# 04_-_RP2040.net
KiCad netlist of a schematic drawn in Altium Designer
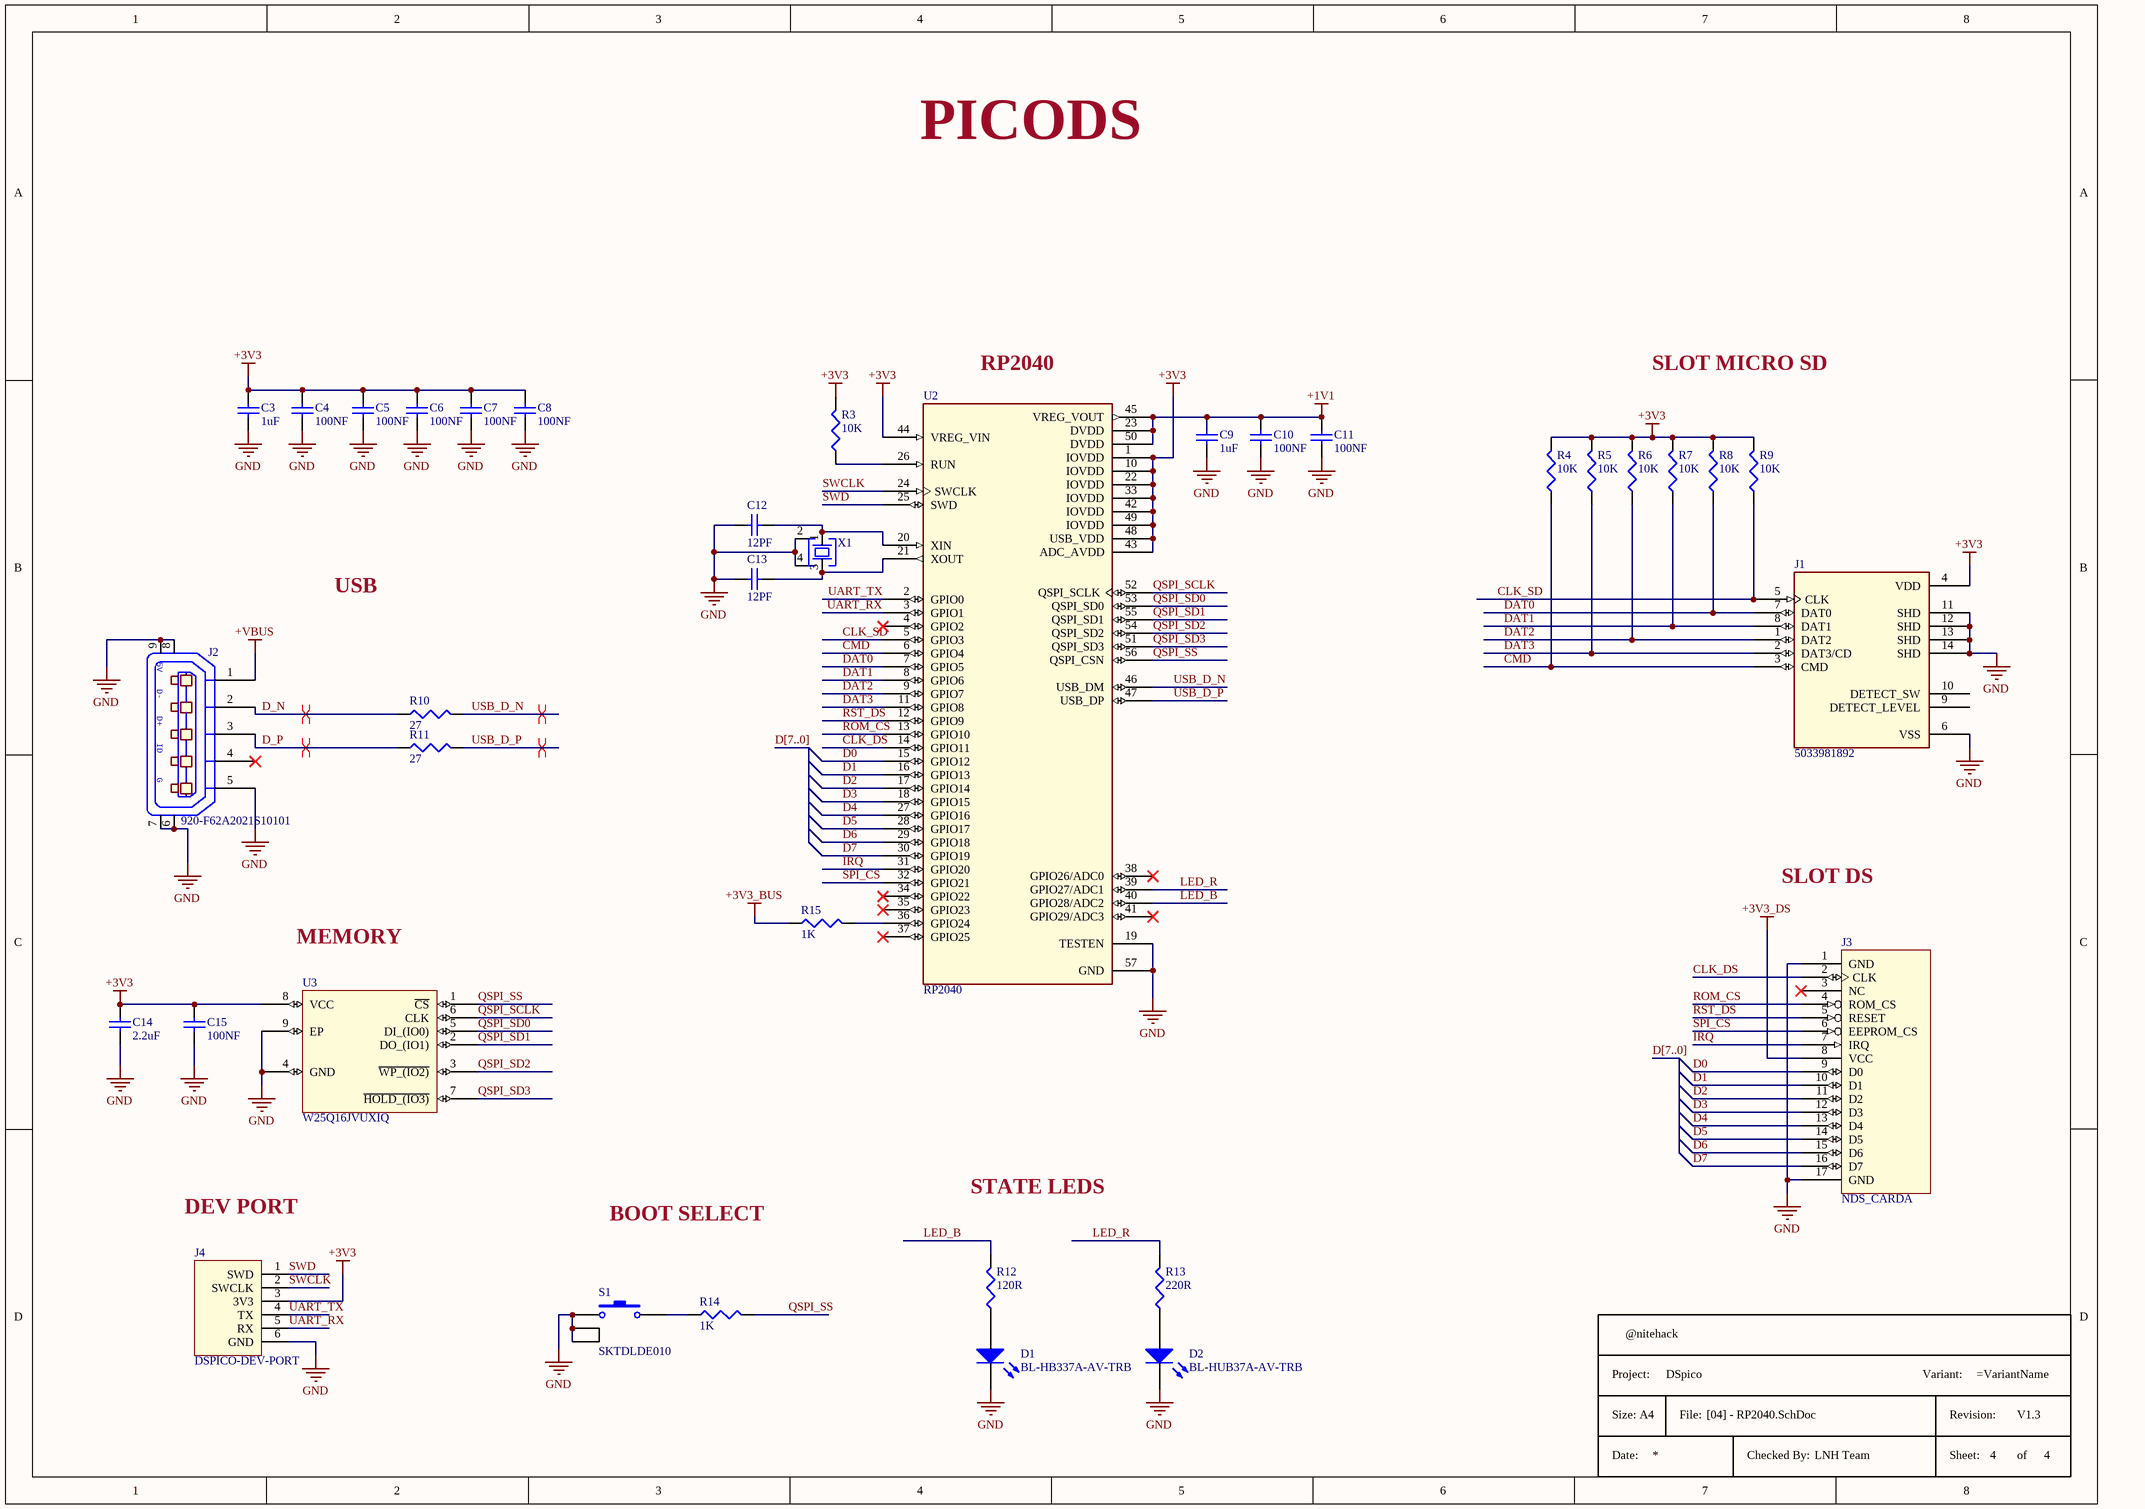
[diagram p0: [04] - RP2040.SchDoc]

(export (version "E")
  (design (tool "Eeschema 10.0.6"))
  (components
    (comp (ref "C3")
      (value "1uF")
      (footprint "C0402")
      (description "TDK - C1005X5R1E105K050BC - COND, CERÁ MULT, X5R, 1UF, 25V, 0402")
      (fields
        (field (name "MANUFACTURER") "TDK")
        (field (name "MANUFACTURER PART NUMBER") "C1005X5R1E105K050BC")
      )
      (libsource (lib "SCHLIB") (part "C1005X5R1E105K050BC"))
    )
    (comp (ref "C4")
      (value "100NF")
      (footprint "C0402")
      (description "0402 0.1 uF 16V ±10 % Tolerance X7R SMT Multilayer Ceramic Capacitor")
      (fields
        (field (name "MANUFACTURER") "Murata")
        (field (name "MANUFACTURER PART NUMBER") "GRM155R71C104KA88D")
      )
      (libsource (lib "SCHLIB") (part "GRM155R71C104KA88D"))
    )
    (comp (ref "C5")
      (value "100NF")
      (footprint "C0402")
      (description "0402 0.1 uF 16V ±10 % Tolerance X7R SMT Multilayer Ceramic Capacitor")
      (fields
        (field (name "MANUFACTURER") "Murata")
        (field (name "MANUFACTURER PART NUMBER") "GRM155R71C104KA88D")
      )
      (libsource (lib "SCHLIB") (part "GRM155R71C104KA88D"))
    )
    (comp (ref "C6")
      (value "100NF")
      (footprint "C0402")
      (description "0402 0.1 uF 16V ±10 % Tolerance X7R SMT Multilayer Ceramic Capacitor")
      (fields
        (field (name "MANUFACTURER") "Murata")
        (field (name "MANUFACTURER PART NUMBER") "GRM155R71C104KA88D")
      )
      (libsource (lib "SCHLIB") (part "GRM155R71C104KA88D"))
    )
    (comp (ref "C7")
      (value "100NF")
      (footprint "C0402")
      (description "0402 0.1 uF 16V ±10 % Tolerance X7R SMT Multilayer Ceramic Capacitor")
      (fields
        (field (name "MANUFACTURER") "Murata")
        (field (name "MANUFACTURER PART NUMBER") "GRM155R71C104KA88D")
      )
      (libsource (lib "SCHLIB") (part "GRM155R71C104KA88D"))
    )
    (comp (ref "C8")
      (value "100NF")
      (footprint "C0402")
      (description "0402 0.1 uF 16V ±10 % Tolerance X7R SMT Multilayer Ceramic Capacitor")
      (fields
        (field (name "MANUFACTURER") "Murata")
        (field (name "MANUFACTURER PART NUMBER") "GRM155R71C104KA88D")
      )
      (libsource (lib "SCHLIB") (part "GRM155R71C104KA88D"))
    )
    (comp (ref "C9")
      (value "1uF")
      (footprint "C0402")
      (description "TDK - C1005X5R1E105K050BC - COND, CERÁ MULT, X5R, 1UF, 25V, 0402")
      (fields
        (field (name "MANUFACTURER") "TDK")
        (field (name "MANUFACTURER PART NUMBER") "C1005X5R1E105K050BC")
      )
      (libsource (lib "SCHLIB") (part "C1005X5R1E105K050BC"))
    )
    (comp (ref "C10")
      (value "100NF")
      (footprint "C0402")
      (description "0402 0.1 uF 16V ±10 % Tolerance X7R SMT Multilayer Ceramic Capacitor")
      (fields
        (field (name "MANUFACTURER") "Murata")
        (field (name "MANUFACTURER PART NUMBER") "GRM155R71C104KA88D")
      )
      (libsource (lib "SCHLIB") (part "GRM155R71C104KA88D"))
    )
    (comp (ref "C11")
      (value "100NF")
      (footprint "C0402")
      (description "0402 0.1 uF 16V ±10 % Tolerance X7R SMT Multilayer Ceramic Capacitor")
      (fields
        (field (name "MANUFACTURER") "Murata")
        (field (name "MANUFACTURER PART NUMBER") "GRM155R71C104KA88D")
      )
      (libsource (lib "SCHLIB") (part "GRM155R71C104KA88D"))
    )
    (comp (ref "C12")
      (value "12PF")
      (footprint "C0402")
      (description "CAP CER 12PF 50V C0G/NP0 0402")
      (fields
        (field (name "MANUFACTURER") "Kyocera AVX")
        (field (name "MANUFACTURER PART NUMBER") "04025A120JAT2A")
      )
      (libsource (lib "SCHLIB") (part "04025A120JAT2A"))
    )
    (comp (ref "C13")
      (value "12PF")
      (footprint "C0402")
      (description "CAP CER 12PF 50V C0G/NP0 0402")
      (fields
        (field (name "MANUFACTURER") "Kyocera AVX")
        (field (name "MANUFACTURER PART NUMBER") "04025A120JAT2A")
      )
      (libsource (lib "SCHLIB") (part "04025A120JAT2A"))
    )
    (comp (ref "C14")
      (value "2.2uF")
      (footprint "C0402")
      (description "TDK - C1005X5R1A225K050BC - COND, CERÁ MULT, X5R, 2.2UF, 10V, 0402")
      (fields
        (field (name "MANUFACTURER") "TDK")
        (field (name "MANUFACTURER PART NUMBER") "C1005X5R1A225K050BC")
        (field (name ".PCBCHECK") "VMM")
        (field (name ".SCHCHECK") "VMM")
      )
      (libsource (lib "SCHLIB") (part "C1005X5R1A225K050BC"))
    )
    (comp (ref "C15")
      (value "100NF")
      (footprint "C0402")
      (description "0402 0.1 uF 16V ±10 % Tolerance X7R SMT Multilayer Ceramic Capacitor")
      (fields
        (field (name "MANUFACTURER") "Murata")
        (field (name "MANUFACTURER PART NUMBER") "GRM155R71C104KA88D")
      )
      (libsource (lib "SCHLIB") (part "GRM155R71C104KA88D"))
    )
    (comp (ref "D1")
      (value "BL-HB337A-AV-TRB")
      (footprint "LED0402-RD")
      (description "Blue 0402 1X.5X4MM")
      (fields (field (name "MANUFACTURER") "American Bright"))
      (libsource (lib "SCHLIB") (part "BL-HB337A-AV-TRB"))
    )
    (comp (ref "D2")
      (value "BL-HUB37A-AV-TRB")
      (footprint "LED0402-RD")
      (description "Red 0402 1X.5X4MM")
      (fields (field (name "MANUFACTURER") "American Bright"))
      (libsource (lib "SCHLIB") (part "BL-HUB37A-AV-TRB"))
    )
    (comp (ref "J1")
      (value "5033981892")
      (footprint "503398-1892_MOL")
      (libsource (lib "SCHLIB") (part "5033981892"))
    )
    (comp (ref "J2")
      (value "920-F62A2021S10101")
      (footprint "MICRO-USB_MICRO-USB-31")
      (libsource (lib "SCHLIB") (part "920-F62A2021S10101"))
    )
    (comp (ref "J3") (value "NDS_CARDA") (footprint "NDS_CARD") (libsource (lib "SCHLIB") (part "NDS_CARDA")))
    (comp (ref "J4")
      (value "DSPICO-DEV-PORT")
      (footprint "EP_DEV_PORT")
      (description "DSpico Development port")
      (fields
        (field (name "MANUFACTURER") "LNH")
        (field (name "MANUFACTURER PART NUMBER") "PICO-DEVELOP-PORT")
      )
      (libsource (lib "SCHLIB") (part "PICO-DEVELOP-PORT"))
    )
    (comp (ref "R3")
      (value "10K")
      (footprint "R0402")
      (description "VISHAY DRALORIC - CRCW040210K0FKED - RESISTENCIA, 10K, 0.063W, 1%, 0402, SMD")
      (fields
        (field (name "MANUFACTURER") "Vishay")
        (field (name "MANUFACTURER PART NUMBER") "CRCW040210K0FKED")
      )
      (libsource (lib "SCHLIB") (part "CRCW040210K0FKED"))
    )
    (comp (ref "R4")
      (value "10K")
      (footprint "R0402")
      (description "VISHAY DRALORIC - CRCW040210K0FKED - RESISTENCIA, 10K, 0.063W, 1%, 0402, SMD")
      (fields
        (field (name "MANUFACTURER") "Vishay")
        (field (name "MANUFACTURER PART NUMBER") "CRCW040210K0FKED")
      )
      (libsource (lib "SCHLIB") (part "CRCW040210K0FKED"))
    )
    (comp (ref "R5")
      (value "10K")
      (footprint "R0402")
      (description "VISHAY DRALORIC - CRCW040210K0FKED - RESISTENCIA, 10K, 0.063W, 1%, 0402, SMD")
      (fields
        (field (name "MANUFACTURER") "Vishay")
        (field (name "MANUFACTURER PART NUMBER") "CRCW040210K0FKED")
      )
      (libsource (lib "SCHLIB") (part "CRCW040210K0FKED"))
    )
    (comp (ref "R6")
      (value "10K")
      (footprint "R0402")
      (description "VISHAY DRALORIC - CRCW040210K0FKED - RESISTENCIA, 10K, 0.063W, 1%, 0402, SMD")
      (fields
        (field (name "MANUFACTURER") "Vishay")
        (field (name "MANUFACTURER PART NUMBER") "CRCW040210K0FKED")
      )
      (libsource (lib "SCHLIB") (part "CRCW040210K0FKED"))
    )
    (comp (ref "R7")
      (value "10K")
      (footprint "R0402")
      (description "VISHAY DRALORIC - CRCW040210K0FKED - RESISTENCIA, 10K, 0.063W, 1%, 0402, SMD")
      (fields
        (field (name "MANUFACTURER") "Vishay")
        (field (name "MANUFACTURER PART NUMBER") "CRCW040210K0FKED")
      )
      (libsource (lib "SCHLIB") (part "CRCW040210K0FKED"))
    )
    (comp (ref "R8")
      (value "10K")
      (footprint "R0402")
      (description "VISHAY DRALORIC - CRCW040210K0FKED - RESISTENCIA, 10K, 0.063W, 1%, 0402, SMD")
      (fields
        (field (name "MANUFACTURER") "Vishay")
        (field (name "MANUFACTURER PART NUMBER") "CRCW040210K0FKED")
      )
      (libsource (lib "SCHLIB") (part "CRCW040210K0FKED"))
    )
    (comp (ref "R9")
      (value "10K")
      (footprint "R0402")
      (description "VISHAY DRALORIC - CRCW040210K0FKED - RESISTENCIA, 10K, 0.063W, 1%, 0402, SMD")
      (fields
        (field (name "MANUFACTURER") "Vishay")
        (field (name "MANUFACTURER PART NUMBER") "CRCW040210K0FKED")
      )
      (libsource (lib "SCHLIB") (part "CRCW040210K0FKED"))
    )
    (comp (ref "R10")
      (value "27")
      (footprint "R0402")
      (description "RES 27 OHM 1% 1/16W 0402")
      (fields (field (name "TOLERANCE") "1%") (field (name "Comment") "RC0402FR-0727RL"))
      (libsource (lib "SCHLIB") (part "RC0402FR-0727RL"))
    )
    (comp (ref "R11")
      (value "27")
      (footprint "R0402")
      (description "RES 27 OHM 1% 1/16W 0402")
      (fields (field (name "TOLERANCE") "1%") (field (name "Comment") "RC0402FR-0727RL"))
      (libsource (lib "SCHLIB") (part "RC0402FR-0727RL"))
    )
    (comp (ref "R12")
      (value "120R")
      (footprint "R0402")
      (description "Res General Purpose Thick Film 0402 120 Ohm 1% 1/16W ±100ppm/°C Molded Paper T/R")
      (fields
        (field (name "MANUFACTURER") "Yageo")
        (field (name "MANUFACTURER PART NUMBER") "RC0402FR-07120RL")
      )
      (libsource (lib "SCHLIB") (part "RC0402FR-07120RL"))
    )
    (comp (ref "R13")
      (value "220R")
      (footprint "R0402")
      (description "SMD Chip Resistor, 220 Ohm, ± 1%, 62.5 mW, 0402 [1005 Metric], Thick Film, General Purpose")
      (fields
        (field (name "MANUFACTURER") "Yageo")
        (field (name "MANUFACTURER PART NUMBER") "RC0402FR-07220RL")
      )
      (libsource (lib "SCHLIB") (part "RC0402FR-07220RL"))
    )
    (comp (ref "R14")
      (value "1K")
      (footprint "R0402")
      (description "VISHAY - CRCW04021K00FKED - RES, PELÍC GRUESA, 1K, 1%, 0.063W, 0402")
      (fields
        (field (name "MANUFACTURER") "VISHAY")
        (field (name "MANUFACTURER PART NUMBER") "CRCW04021K00FKED")
      )
      (libsource (lib "SCHLIB") (part "CRCW04021K00FKEDC"))
    )
    (comp (ref "R15")
      (value "1K")
      (footprint "R0402")
      (description "VISHAY - CRCW04021K00FKED - RES, PELÍC GRUESA, 1K, 1%, 0.063W, 0402")
      (fields
        (field (name "MANUFACTURER") "VISHAY")
        (field (name "MANUFACTURER PART NUMBER") "CRCW04021K00FKED")
      )
      (libsource (lib "SCHLIB") (part "CRCW04021K00FKEDC"))
    )
    (comp (ref "S1")
      (value "SKTDLDE010")
      (footprint "KEY-SMD_SKTDLDE010")
      (description "Switch Tactile N.O. SPST Rectangular Button Gull Wing 0.05A 12VDC 1.6N SMD T/R")
      (fields (field (name "MANUFACTURER") "Alps Electric"))
      (libsource (lib "SCHLIB") (part "SKTDLDE010"))
    )
    (comp (ref "U2")
      (value "RP2040")
      (footprint "QFN40P700X700X90-57N")
      (description "RP2040 chip for Raspberry Pi Pico - ARM Cortex-M0+ MCU 32-Bit")
      (fields (field (name "MF") "Raspberry Pi"))
      (libsource (lib "SCHLIB") (part "RP2040"))
    )
    (comp (ref "U3")
      (value "W25Q16JVUXIQ")
      (footprint "SON50P300X200X60-9N")
      (description "NOR Flash Serial (SPI, Dual SPI, Quad SPI) 3V/3.3V 16M-bit 2M x 8 6ns 8-Pin USON EP T/R")
      (fields (field (name "MF") "Winbond"))
      (libsource (lib "SCHLIB") (part "W25Q16JVUXIQ"))
    )
    (comp (ref "X1")
      (value "XYDBPCNANF-12MHZ")
      (footprint "OSC-SMD_4P-L2.5-W2.0-BL")
      (libsource (lib "SCHLIB") (part "XYDBPCNANF-12MHZ"))
    )
  )
  (nets
    (net (code "1") (name "+1V1") (class "Default")
      (node (ref "C10") (pin "2") (pinfunction "2_2") (pintype "passive"))
      (node (ref "C11") (pin "2") (pinfunction "2_2") (pintype "passive"))
      (node (ref "C9") (pin "2") (pinfunction "2_2") (pintype "passive"))
      (node (ref "U2") (pin "23") (pinfunction "DVDD_23") (pintype "power_in"))
      (node (ref "U2") (pin "45") (pinfunction "VREG_VOUT_45") (pintype "output"))
      (node (ref "U2") (pin "50") (pinfunction "DVDD_50") (pintype "power_in"))
    )
    (net (code "2") (name "+3V3") (class "Default")
      (node (ref "C14") (pin "2") (pinfunction "2_2") (pintype "passive"))
      (node (ref "C15") (pin "2") (pinfunction "2_2") (pintype "passive"))
      (node (ref "C3") (pin "2") (pinfunction "2_2") (pintype "passive"))
      (node (ref "C4") (pin "2") (pinfunction "2_2") (pintype "passive"))
      (node (ref "C5") (pin "2") (pinfunction "2_2") (pintype "passive"))
      (node (ref "C6") (pin "2") (pinfunction "2_2") (pintype "passive"))
      (node (ref "C7") (pin "2") (pinfunction "2_2") (pintype "passive"))
      (node (ref "C8") (pin "2") (pinfunction "2_2") (pintype "passive"))
      (node (ref "J1") (pin "4") (pinfunction "VDD_4") (pintype "power_in"))
      (node (ref "J4") (pin "3") (pinfunction "3V3_3") (pintype "passive"))
      (node (ref "R3") (pin "2") (pinfunction "2_2") (pintype "passive"))
      (node (ref "R4") (pin "2") (pinfunction "2_2") (pintype "passive"))
      (node (ref "R5") (pin "2") (pinfunction "2_2") (pintype "passive"))
      (node (ref "R6") (pin "2") (pinfunction "2_2") (pintype "passive"))
      (node (ref "R7") (pin "2") (pinfunction "2_2") (pintype "passive"))
      (node (ref "R8") (pin "2") (pinfunction "2_2") (pintype "passive"))
      (node (ref "R9") (pin "2") (pinfunction "2_2") (pintype "passive"))
      (node (ref "U2") (pin "1") (pinfunction "IOVDD_1") (pintype "power_in"))
      (node (ref "U2") (pin "10") (pinfunction "IOVDD_10") (pintype "power_in"))
      (node (ref "U2") (pin "22") (pinfunction "IOVDD_22") (pintype "power_in"))
      (node (ref "U2") (pin "33") (pinfunction "IOVDD_33") (pintype "power_in"))
      (node (ref "U2") (pin "42") (pinfunction "IOVDD_42") (pintype "power_in"))
      (node (ref "U2") (pin "43") (pinfunction "ADC_AVDD_43") (pintype "power_in"))
      (node (ref "U2") (pin "44") (pinfunction "VREG_VIN_44") (pintype "input"))
      (node (ref "U2") (pin "48") (pinfunction "USB_VDD_48") (pintype "power_in"))
      (node (ref "U2") (pin "49") (pinfunction "IOVDD_49") (pintype "power_in"))
      (node (ref "U3") (pin "8") (pinfunction "VCC_8") (pintype "bidirectional"))
    )
    (net (code "3") (name "+3V3_BUS") (class "Default")
      (node (ref "R15") (pin "1") (pinfunction "1_1") (pintype "passive"))
    )
    (net (code "4") (name "+3V3_DS") (class "Default")
      (node (ref "J3") (pin "8") (pinfunction "VCC_8") (pintype "power_in"))
    )
    (net (code "5") (name "+VBUS") (class "Default")
      (node (ref "J2") (pin "1") (pinfunction "P1_1") (pintype "passive"))
    )
    (net (code "6") (name "/CLK_DS") (class "Default")
      (node (ref "J3") (pin "2") (pinfunction "CLK_2") (pintype "bidirectional"))
      (node (ref "U2") (pin "14") (pinfunction "GPIO11_14") (pintype "bidirectional"))
    )
    (net (code "7") (name "/CLK_SD") (class "Default")
      (node (ref "J1") (pin "5") (pinfunction "CLK_5") (pintype "input"))
      (node (ref "R9") (pin "1") (pinfunction "1_1") (pintype "passive"))
      (node (ref "U2") (pin "5") (pinfunction "GPIO3_5") (pintype "bidirectional"))
    )
    (net (code "8") (name "/CMD") (class "Default")
      (node (ref "J1") (pin "3") (pinfunction "CMD_3") (pintype "bidirectional"))
      (node (ref "R4") (pin "1") (pinfunction "1_1") (pintype "passive"))
      (node (ref "U2") (pin "6") (pinfunction "GPIO4_6") (pintype "bidirectional"))
    )
    (net (code "9") (name "/D0") (class "Default")
      (node (ref "J3") (pin "9") (pinfunction "D0_9") (pintype "bidirectional"))
      (node (ref "U2") (pin "15") (pinfunction "GPIO12_15") (pintype "bidirectional"))
    )
    (net (code "10") (name "/D1") (class "Default")
      (node (ref "J3") (pin "10") (pinfunction "D1_10") (pintype "bidirectional"))
      (node (ref "U2") (pin "16") (pinfunction "GPIO13_16") (pintype "bidirectional"))
    )
    (net (code "11") (name "/D2") (class "Default")
      (node (ref "J3") (pin "11") (pinfunction "D2_11") (pintype "bidirectional"))
      (node (ref "U2") (pin "17") (pinfunction "GPIO14_17") (pintype "bidirectional"))
    )
    (net (code "12") (name "/D3") (class "Default")
      (node (ref "J3") (pin "12") (pinfunction "D3_12") (pintype "bidirectional"))
      (node (ref "U2") (pin "18") (pinfunction "GPIO15_18") (pintype "bidirectional"))
    )
    (net (code "13") (name "/D4") (class "Default")
      (node (ref "J3") (pin "13") (pinfunction "D4_13") (pintype "bidirectional"))
      (node (ref "U2") (pin "27") (pinfunction "GPIO16_27") (pintype "bidirectional"))
    )
    (net (code "14") (name "/D5") (class "Default")
      (node (ref "J3") (pin "14") (pinfunction "D5_14") (pintype "bidirectional"))
      (node (ref "U2") (pin "28") (pinfunction "GPIO17_28") (pintype "bidirectional"))
    )
    (net (code "15") (name "/D6") (class "Default")
      (node (ref "J3") (pin "15") (pinfunction "D6_15") (pintype "bidirectional"))
      (node (ref "U2") (pin "29") (pinfunction "GPIO18_29") (pintype "bidirectional"))
    )
    (net (code "16") (name "/D7") (class "Default")
      (node (ref "J3") (pin "16") (pinfunction "D7_16") (pintype "bidirectional"))
      (node (ref "U2") (pin "30") (pinfunction "GPIO19_30") (pintype "bidirectional"))
    )
    (net (code "17") (name "/DAT0") (class "Default")
      (node (ref "J1") (pin "7") (pinfunction "DAT0_7") (pintype "bidirectional"))
      (node (ref "R8") (pin "1") (pinfunction "1_1") (pintype "passive"))
      (node (ref "U2") (pin "7") (pinfunction "GPIO5_7") (pintype "bidirectional"))
    )
    (net (code "18") (name "/DAT1") (class "Default")
      (node (ref "J1") (pin "8") (pinfunction "DAT1_8") (pintype "bidirectional"))
      (node (ref "R7") (pin "1") (pinfunction "1_1") (pintype "passive"))
      (node (ref "U2") (pin "8") (pinfunction "GPIO6_8") (pintype "bidirectional"))
    )
    (net (code "19") (name "/DAT2") (class "Default")
      (node (ref "J1") (pin "1") (pinfunction "DAT2_1") (pintype "bidirectional"))
      (node (ref "R6") (pin "1") (pinfunction "1_1") (pintype "passive"))
      (node (ref "U2") (pin "9") (pinfunction "GPIO7_9") (pintype "bidirectional"))
    )
    (net (code "20") (name "/DAT3") (class "Default")
      (node (ref "J1") (pin "2") (pinfunction "DAT3/CD_2") (pintype "bidirectional"))
      (node (ref "R5") (pin "1") (pinfunction "1_1") (pintype "passive"))
      (node (ref "U2") (pin "11") (pinfunction "GPIO8_11") (pintype "bidirectional"))
    )
    (net (code "22") (name "/D_N") (class "Default")
      (node (ref "J2") (pin "2") (pinfunction "P2_2") (pintype "passive"))
      (node (ref "R10") (pin "1") (pinfunction "1_1") (pintype "passive"))
    )
    (net (code "23") (name "/D_P") (class "Default")
      (node (ref "J2") (pin "3") (pinfunction "P3_3") (pintype "passive"))
      (node (ref "R11") (pin "1") (pinfunction "1_1") (pintype "passive"))
    )
    (net (code "24") (name "/IRQ") (class "Default")
      (node (ref "J3") (pin "7") (pinfunction "IRQ_7") (pintype "input"))
      (node (ref "U2") (pin "31") (pinfunction "GPIO20_31") (pintype "bidirectional"))
    )
    (net (code "25") (name "/LED_B") (class "Default")
      (node (ref "R12") (pin "2") (pinfunction "2_2") (pintype "passive"))
      (node (ref "U2") (pin "40") (pinfunction "GPIO28/ADC2_40") (pintype "bidirectional"))
    )
    (net (code "26") (name "/LED_R") (class "Default")
      (node (ref "R13") (pin "2") (pinfunction "2_2") (pintype "passive"))
      (node (ref "U2") (pin "39") (pinfunction "GPIO27/ADC1_39") (pintype "bidirectional"))
    )
    (net (code "27") (name "/QSPI_SCLK") (class "Default")
      (node (ref "U2") (pin "52") (pinfunction "QSPI_SCLK_52") (pintype "bidirectional"))
      (node (ref "U3") (pin "6") (pinfunction "CLK_6") (pintype "bidirectional"))
    )
    (net (code "28") (name "/QSPI_SD0") (class "Default")
      (node (ref "U2") (pin "53") (pinfunction "QSPI_SD0_53") (pintype "bidirectional"))
      (node (ref "U3") (pin "5") (pinfunction "DI_(IO0)_5") (pintype "bidirectional"))
    )
    (net (code "29") (name "/QSPI_SD1") (class "Default")
      (node (ref "U2") (pin "55") (pinfunction "QSPI_SD1_55") (pintype "bidirectional"))
      (node (ref "U3") (pin "2") (pinfunction "DO_(IO1)_2") (pintype "bidirectional"))
    )
    (net (code "30") (name "/QSPI_SD2") (class "Default")
      (node (ref "U2") (pin "54") (pinfunction "QSPI_SD2_54") (pintype "bidirectional"))
      (node (ref "U3") (pin "3") (pinfunction "~{WP_(IO2)}_3") (pintype "bidirectional"))
    )
    (net (code "31") (name "/QSPI_SD3") (class "Default")
      (node (ref "U2") (pin "51") (pinfunction "QSPI_SD3_51") (pintype "bidirectional"))
      (node (ref "U3") (pin "7") (pinfunction "~{HOLD_(IO3)}_7") (pintype "bidirectional"))
    )
    (net (code "32") (name "/QSPI_SS") (class "Default")
      (node (ref "R14") (pin "2") (pinfunction "2_2") (pintype "passive"))
      (node (ref "U2") (pin "56") (pinfunction "QSPI_CSN_56") (pintype "bidirectional"))
      (node (ref "U3") (pin "1") (pinfunction "~{CS}_1") (pintype "bidirectional"))
    )
    (net (code "33") (name "/ROM_CS") (class "Default")
      (node (ref "J3") (pin "4") (pinfunction "ROM_CS_4") (pintype "input"))
      (node (ref "U2") (pin "13") (pinfunction "GPIO10_13") (pintype "bidirectional"))
    )
    (net (code "34") (name "/RST_DS") (class "Default")
      (node (ref "J3") (pin "5") (pinfunction "RESET_5") (pintype "input"))
      (node (ref "U2") (pin "12") (pinfunction "GPIO9_12") (pintype "bidirectional"))
    )
    (net (code "35") (name "/SPI_CS") (class "Default")
      (node (ref "J3") (pin "6") (pinfunction "EEPROM_CS_6") (pintype "input"))
      (node (ref "U2") (pin "32") (pinfunction "GPIO21_32") (pintype "bidirectional"))
    )
    (net (code "36") (name "/SWCLK") (class "Default")
      (node (ref "J4") (pin "2") (pinfunction "SWCLK_2") (pintype "passive"))
      (node (ref "U2") (pin "24") (pinfunction "SWCLK_24") (pintype "input"))
    )
    (net (code "37") (name "/SWD") (class "Default")
      (node (ref "J4") (pin "1") (pinfunction "SWD_1") (pintype "passive"))
      (node (ref "U2") (pin "25") (pinfunction "SWD_25") (pintype "bidirectional"))
    )
    (net (code "38") (name "/UART_RX") (class "Default")
      (node (ref "J4") (pin "5") (pinfunction "RX_5") (pintype "passive"))
      (node (ref "U2") (pin "3") (pinfunction "GPIO1_3") (pintype "bidirectional"))
    )
    (net (code "39") (name "/UART_TX") (class "Default")
      (node (ref "J4") (pin "4") (pinfunction "TX_4") (pintype "passive"))
      (node (ref "U2") (pin "2") (pinfunction "GPIO0_2") (pintype "bidirectional"))
    )
    (net (code "40") (name "/USB_D_N") (class "Default")
      (node (ref "R10") (pin "2") (pinfunction "2_2") (pintype "passive"))
      (node (ref "U2") (pin "46") (pinfunction "USB_DM_46") (pintype "bidirectional"))
    )
    (net (code "41") (name "/USB_D_P") (class "Default")
      (node (ref "R11") (pin "2") (pinfunction "2_2") (pintype "passive"))
      (node (ref "U2") (pin "47") (pinfunction "USB_DP_47") (pintype "bidirectional"))
    )
    (net (code "42") (name "GND") (class "Default")
      (node (ref "C10") (pin "1") (pinfunction "1_1") (pintype "passive"))
      (node (ref "C11") (pin "1") (pinfunction "1_1") (pintype "passive"))
      (node (ref "C12") (pin "1") (pinfunction "1_1") (pintype "passive"))
      (node (ref "C13") (pin "1") (pinfunction "1_1") (pintype "passive"))
      (node (ref "C14") (pin "1") (pinfunction "1_1") (pintype "passive"))
      (node (ref "C15") (pin "1") (pinfunction "1_1") (pintype "passive"))
      (node (ref "C3") (pin "1") (pinfunction "1_1") (pintype "passive"))
      (node (ref "C4") (pin "1") (pinfunction "1_1") (pintype "passive"))
      (node (ref "C5") (pin "1") (pinfunction "1_1") (pintype "passive"))
      (node (ref "C6") (pin "1") (pinfunction "1_1") (pintype "passive"))
      (node (ref "C7") (pin "1") (pinfunction "1_1") (pintype "passive"))
      (node (ref "C8") (pin "1") (pinfunction "1_1") (pintype "passive"))
      (node (ref "C9") (pin "1") (pinfunction "1_1") (pintype "passive"))
      (node (ref "D1") (pin "1") (pinfunction "1_1") (pintype "passive"))
      (node (ref "D2") (pin "1") (pinfunction "1_1") (pintype "passive"))
      (node (ref "J1") (pin "11") (pinfunction "SHD_11") (pintype "passive"))
      (node (ref "J1") (pin "12") (pinfunction "SHD_12") (pintype "passive"))
      (node (ref "J1") (pin "13") (pinfunction "SHD_13") (pintype "passive"))
      (node (ref "J1") (pin "14") (pinfunction "SHD_14") (pintype "passive"))
      (node (ref "J1") (pin "6") (pinfunction "VSS_6") (pintype "power_in"))
      (node (ref "J2") (pin "5") (pinfunction "P5_5") (pintype "passive"))
      (node (ref "J2") (pin "6") (pinfunction "6_6") (pintype "passive"))
      (node (ref "J2") (pin "7") (pinfunction "7_7") (pintype "passive"))
      (node (ref "J2") (pin "8") (pinfunction "8_8") (pintype "passive"))
      (node (ref "J2") (pin "9") (pinfunction "9_9") (pintype "passive"))
      (node (ref "J3") (pin "1") (pinfunction "GND_1") (pintype "power_in"))
      (node (ref "J3") (pin "17") (pinfunction "GND_17") (pintype "power_in"))
      (node (ref "J4") (pin "6") (pinfunction "GND_6") (pintype "passive"))
      (node (ref "S1") (pin "1") (pinfunction "1_1") (pintype "passive"))
      (node (ref "S1") (pin "3") (pinfunction "3_3") (pintype "passive"))
      (node (ref "S1") (pin "4") (pinfunction "4_4") (pintype "passive"))
      (node (ref "U2") (pin "19") (pinfunction "TESTEN_19") (pintype "passive"))
      (node (ref "U2") (pin "57") (pinfunction "GND_57") (pintype "power_in"))
      (node (ref "U3") (pin "4") (pinfunction "GND_4") (pintype "bidirectional"))
      (node (ref "U3") (pin "9") (pinfunction "EP_9") (pintype "bidirectional"))
      (node (ref "X1") (pin "2") (pinfunction "2_2") (pintype "passive"))
      (node (ref "X1") (pin "4") (pinfunction "4_4") (pintype "passive"))
    )
    (net (code "43") (name "Net-(D1-Pad2)") (class "Default")
      (node (ref "D1") (pin "2") (pinfunction "2_2") (pintype "passive"))
      (node (ref "R12") (pin "1") (pinfunction "1_1") (pintype "passive"))
    )
    (net (code "44") (name "Net-(D2-Pad2)") (class "Default")
      (node (ref "D2") (pin "2") (pinfunction "2_2") (pintype "passive"))
      (node (ref "R13") (pin "1") (pinfunction "1_1") (pintype "passive"))
    )
    (net (code "45") (name "Net-(R14-Pad1)") (class "Default")
      (node (ref "R14") (pin "1") (pinfunction "1_1") (pintype "passive"))
      (node (ref "S1") (pin "2") (pinfunction "2_2") (pintype "passive"))
    )
    (net (code "46") (name "Net-(U2-GPIO24)") (class "Default")
      (node (ref "R15") (pin "2") (pinfunction "2_2") (pintype "passive"))
      (node (ref "U2") (pin "36") (pinfunction "GPIO24_36") (pintype "bidirectional"))
    )
    (net (code "47") (name "Net-(U2-RUN)") (class "Default")
      (node (ref "R3") (pin "1") (pinfunction "1_1") (pintype "passive"))
      (node (ref "U2") (pin "26") (pinfunction "RUN_26") (pintype "input"))
    )
    (net (code "48") (name "Net-(U2-XIN)") (class "Default")
      (node (ref "C12") (pin "2") (pinfunction "2_2") (pintype "passive"))
      (node (ref "U2") (pin "20") (pinfunction "XIN_20") (pintype "input"))
      (node (ref "X1") (pin "1") (pinfunction "1_1") (pintype "passive"))
    )
    (net (code "49") (name "Net-(U2-XOUT)") (class "Default")
      (node (ref "C13") (pin "2") (pinfunction "2_2") (pintype "passive"))
      (node (ref "U2") (pin "21") (pinfunction "XOUT_21") (pintype "output"))
      (node (ref "X1") (pin "3") (pinfunction "3_3") (pintype "passive"))
    )
    (net (code "50") (name "unconnected-(J1-DETECT_LEVEL-Pad9)") (class "Default")
      (node (ref "J1") (pin "9") (pinfunction "DETECT_LEVEL_9") (pintype "passive"))
    )
    (net (code "51") (name "unconnected-(J1-DETECT_SW-Pad10)") (class "Default")
      (node (ref "J1") (pin "10") (pinfunction "DETECT_SW_10") (pintype "passive"))
    )
    (net (code "52") (name "unconnected-(J2-P4-Pad4)") (class "Default")
      (node (ref "J2") (pin "4") (pinfunction "P4_4") (pintype "passive+no_connect"))
    )
    (net (code "53") (name "unconnected-(J3-NC-Pad3)") (class "Default")
      (node (ref "J3") (pin "3") (pinfunction "NC_3") (pintype "passive+no_connect"))
    )
    (net (code "54") (name "unconnected-(U2-GPIO2-Pad4)") (class "Default")
      (node (ref "U2") (pin "4") (pinfunction "GPIO2_4") (pintype "bidirectional+no_connect"))
    )
    (net (code "55") (name "unconnected-(U2-GPIO22-Pad34)") (class "Default")
      (node (ref "U2") (pin "34") (pinfunction "GPIO22_34") (pintype "bidirectional+no_connect"))
    )
    (net (code "56") (name "unconnected-(U2-GPIO23-Pad35)") (class "Default")
      (node (ref "U2") (pin "35") (pinfunction "GPIO23_35") (pintype "bidirectional+no_connect"))
    )
    (net (code "57") (name "unconnected-(U2-GPIO25-Pad37)") (class "Default")
      (node (ref "U2") (pin "37") (pinfunction "GPIO25_37") (pintype "bidirectional+no_connect"))
    )
    (net (code "58") (name "unconnected-(U2-GPIO26{slash}ADC0-Pad38)") (class "Default")
      (node (ref "U2") (pin "38") (pinfunction "GPIO26/ADC0_38") (pintype "bidirectional+no_connect"))
    )
    (net (code "59") (name "unconnected-(U2-GPIO29{slash}ADC3-Pad41)") (class "Default")
      (node (ref "U2") (pin "41") (pinfunction "GPIO29/ADC3_41") (pintype "bidirectional+no_connect"))
    )
  )
)
